# atWork_Motor_Driver.net
KiCad netlist of a schematic drawn in Altium Designer
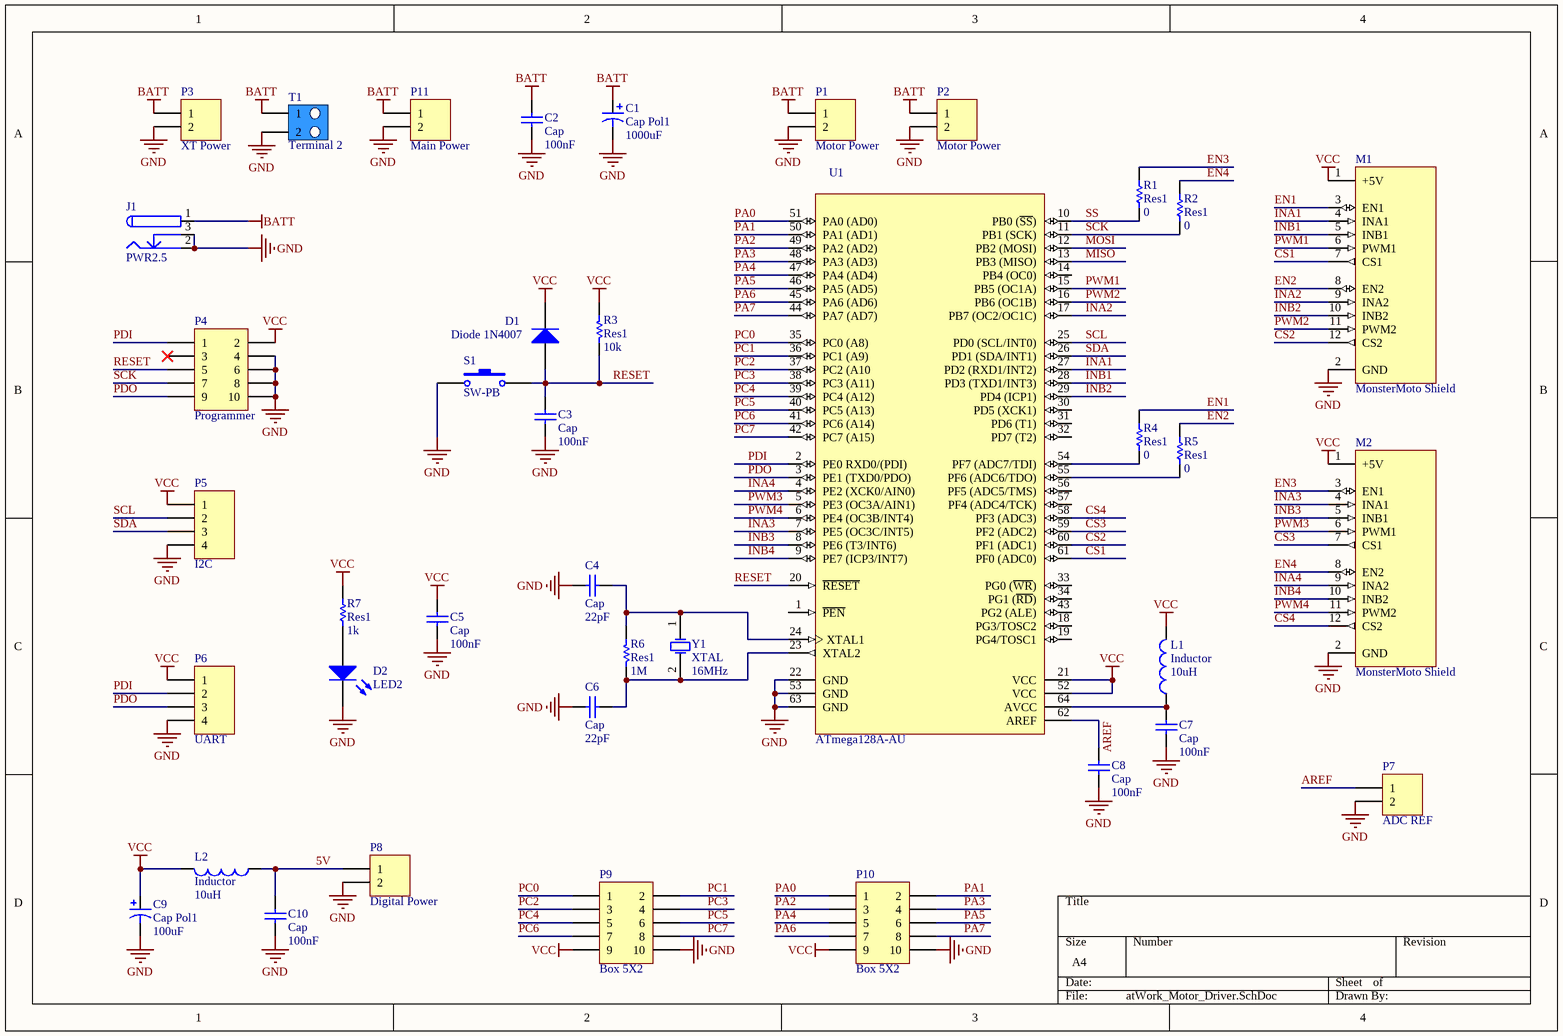
[diagram p0: atWork_Motor_Driver.SchDoc]

(export (version "E")
  (design (tool "Eeschema 10.0.6"))
  (components
    (comp (ref "C1")
      (value "Cap Pol1")
      (footprint "CAP2")
      (description "Polarized Capacitor (Radial)")
      (fields (field (name "ALTIUM_VALUE") "1000uF") (field (name "PUBLISHER") "Altium Limited"))
      (libsource (lib "Miscellaneous Devices") (part "Cap Pol1"))
    )
    (comp (ref "C2")
      (value "Cap")
      (footprint "C1206")
      (description "Capacitor")
      (fields (field (name "ALTIUM_VALUE") "100nF") (field (name "PUBLISHER") "Altium Limited"))
      (libsource (lib "Miscellaneous Devices") (part "Cap"))
    )
    (comp (ref "C3")
      (value "Cap")
      (footprint "C1206")
      (description "Capacitor")
      (fields (field (name "ALTIUM_VALUE") "100nF") (field (name "PUBLISHER") "Altium Limited"))
      (libsource (lib "Miscellaneous Devices") (part "Cap"))
    )
    (comp (ref "C4")
      (value "Cap")
      (footprint "C1206")
      (description "Capacitor")
      (fields (field (name "ALTIUM_VALUE") "22pF") (field (name "PUBLISHER") "Altium Limited"))
      (libsource (lib "Miscellaneous Devices") (part "Cap"))
    )
    (comp (ref "C5")
      (value "Cap")
      (footprint "C1206")
      (description "Capacitor")
      (fields (field (name "ALTIUM_VALUE") "100nF") (field (name "PUBLISHER") "Altium Limited"))
      (libsource (lib "Miscellaneous Devices") (part "Cap"))
    )
    (comp (ref "C6")
      (value "Cap")
      (footprint "C1206")
      (description "Capacitor")
      (fields (field (name "ALTIUM_VALUE") "22pF") (field (name "PUBLISHER") "Altium Limited"))
      (libsource (lib "Miscellaneous Devices") (part "Cap"))
    )
    (comp (ref "C7")
      (value "Cap")
      (footprint "C1206")
      (description "Capacitor")
      (fields (field (name "ALTIUM_VALUE") "100nF") (field (name "PUBLISHER") "Altium Limited"))
      (libsource (lib "Miscellaneous Devices") (part "Cap"))
    )
    (comp (ref "C8")
      (value "Cap")
      (footprint "C1206")
      (description "Capacitor")
      (fields (field (name "ALTIUM_VALUE") "100nF") (field (name "PUBLISHER") "Altium Limited"))
      (libsource (lib "Miscellaneous Devices") (part "Cap"))
    )
    (comp (ref "C9")
      (value "Cap Pol1")
      (footprint "CAP-SMD1")
      (description "Polarized Capacitor (Radial)")
      (fields (field (name "ALTIUM_VALUE") "100uF") (field (name "PUBLISHER") "Altium Limited"))
      (libsource (lib "") (part "Cap Pol1_1"))
    )
    (comp (ref "C10")
      (value "Cap")
      (footprint "C1206")
      (description "Capacitor")
      (fields (field (name "ALTIUM_VALUE") "100nF") (field (name "PUBLISHER") "Altium Limited"))
      (libsource (lib "Miscellaneous Devices") (part "Cap"))
    )
    (comp (ref "D1")
      (value "Diode 1N4007")
      (footprint "DIODE-SMD")
      (description "1 Amp General Purpose Rectifier")
      (fields (field (name "PUBLISHER") "Altium Limited"))
      (libsource (lib "Miscellaneous Devices") (part "Diode 1N4007"))
    )
    (comp (ref "D2")
      (value "LED2")
      (footprint "3.2X1.6X1.1")
      (description "Typical RED, GREEN, YELLOW, AMBER GaAs LED")
      (fields (field (name "PUBLISHER") "Altium Limited"))
      (libsource (lib "Miscellaneous Devices") (part "LED2"))
    )
    (comp (ref "J1")
      (value "PWR2.5")
      (footprint "PWR2.5")
      (description "Low Voltage Power Supply Connector")
      (fields (field (name "PUBLISHER") "Altium Limited"))
      (libsource (lib "mp") (part "PWR2.5"))
    )
    (comp (ref "L1")
      (value "Inductor")
      (footprint "C1206")
      (fields (field (name "ALTIUM_VALUE") "10uH") (field (name "PUBLISHER") "Altium Limited"))
      (libsource (lib "Miscellaneous Devices") (part "Inductor"))
    )
    (comp (ref "L2")
      (value "Inductor")
      (footprint "C1206")
      (fields (field (name "ALTIUM_VALUE") "10uH") (field (name "PUBLISHER") "Altium Limited"))
      (libsource (lib "Miscellaneous Devices") (part "Inductor"))
    )
    (comp (ref "M1")
      (value "MonsterMoto Shield")
      (footprint "MONSTERMOTO")
      (fields (field (name "DESIGNER") "Meysam Parvizi") (field (name "EMAIL") "meysam.parvizi@live.com"))
      (libsource (lib "mp") (part "MonsterMoto"))
    )
    (comp (ref "M2")
      (value "MonsterMoto Shield")
      (footprint "MONSTERMOTO")
      (fields (field (name "DESIGNER") "Meysam Parvizi") (field (name "EMAIL") "meysam.parvizi@live.com"))
      (libsource (lib "mp") (part "MonsterMoto"))
    )
    (comp (ref "P1")
      (value "Motor Power")
      (footprint "POWER2PIN")
      (description "Header, 2-Pin")
      (fields (field (name "PUBLISHER") "Altium Limited"))
      (libsource (lib "Miscellaneous Connectors") (part "Header 2"))
    )
    (comp (ref "P2")
      (value "Motor Power")
      (footprint "POWER2PIN")
      (description "Header, 2-Pin")
      (fields (field (name "PUBLISHER") "Altium Limited"))
      (libsource (lib "Miscellaneous Connectors") (part "Header 2"))
    )
    (comp (ref "P3")
      (value "XT Power")
      (footprint "XT")
      (description "Header, 2-Pin")
      (fields (field (name "PUBLISHER") "Altium Limited"))
      (libsource (lib "Miscellaneous Connectors") (part "Header 2"))
    )
    (comp (ref "P4")
      (value "Programmer")
      (footprint "BOX2X5")
      (description "Box, 5-Pin, Dual row")
      (fields (field (name "DESIGNER") "Meysam Parvizi") (field (name "EMAIL") "meysam.parvizi.ir@gmail.com"))
      (libsource (lib "mp") (part "Box 5X2"))
    )
    (comp (ref "P5")
      (value "I2C")
      (footprint "XH4PIN")
      (description "Header, 4-Pin")
      (fields (field (name "PUBLISHER") "Altium Limited"))
      (libsource (lib "Miscellaneous Connectors") (part "Header 4"))
    )
    (comp (ref "P6")
      (value "UART")
      (footprint "XH4PIN")
      (description "Header, 4-Pin")
      (fields (field (name "PUBLISHER") "Altium Limited"))
      (libsource (lib "Miscellaneous Connectors") (part "Header 4"))
    )
    (comp (ref "P7")
      (value "ADC REF")
      (footprint "XH2PIN")
      (description "Header, 2-Pin")
      (fields (field (name "PUBLISHER") "Altium Limited"))
      (libsource (lib "Miscellaneous Connectors") (part "Header 2"))
    )
    (comp (ref "P8")
      (value "Digital Power")
      (footprint "XH2PIN")
      (description "Header, 2-Pin")
      (fields (field (name "PUBLISHER") "Altium Limited"))
      (libsource (lib "Miscellaneous Connectors") (part "Header 2"))
    )
    (comp (ref "P9")
      (value "Box 5X2")
      (footprint "BOX2X5_RIGHT")
      (description "Box, 5-Pin, Dual row")
      (fields (field (name "DESIGNER") "Meysam Parvizi") (field (name "EMAIL") "meysam.parvizi.ir@gmail.com"))
      (libsource (lib "mp") (part "Box 5X2"))
    )
    (comp (ref "P10")
      (value "Box 5X2")
      (footprint "BOX2X5_RIGHT")
      (description "Box, 5-Pin, Dual row")
      (fields (field (name "DESIGNER") "Meysam Parvizi") (field (name "EMAIL") "meysam.parvizi.ir@gmail.com"))
      (libsource (lib "mp") (part "Box 5X2"))
    )
    (comp (ref "P11")
      (value "Main Power")
      (footprint "POWER2PIN")
      (description "Header, 2-Pin")
      (fields (field (name "PUBLISHER") "Altium Limited"))
      (libsource (lib "Miscellaneous Connectors") (part "Header 2"))
    )
    (comp (ref "R1")
      (value "Res1")
      (footprint "C1206")
      (description "Resistor")
      (fields (field (name "ALTIUM_VALUE") "0") (field (name "PUBLISHER") "Altium Limited"))
      (libsource (lib "Miscellaneous Devices") (part "Res1"))
    )
    (comp (ref "R2")
      (value "Res1")
      (footprint "C1206")
      (description "Resistor")
      (fields (field (name "ALTIUM_VALUE") "0") (field (name "PUBLISHER") "Altium Limited"))
      (libsource (lib "Miscellaneous Devices") (part "Res1"))
    )
    (comp (ref "R3")
      (value "Res1")
      (footprint "C1206")
      (description "Resistor")
      (fields (field (name "ALTIUM_VALUE") "10k") (field (name "PUBLISHER") "Altium Limited"))
      (libsource (lib "Miscellaneous Devices") (part "Res1"))
    )
    (comp (ref "R4")
      (value "Res1")
      (footprint "C1206")
      (description "Resistor")
      (fields (field (name "ALTIUM_VALUE") "0") (field (name "PUBLISHER") "Altium Limited"))
      (libsource (lib "Miscellaneous Devices") (part "Res1"))
    )
    (comp (ref "R5")
      (value "Res1")
      (footprint "C1206")
      (description "Resistor")
      (fields (field (name "ALTIUM_VALUE") "0") (field (name "PUBLISHER") "Altium Limited"))
      (libsource (lib "Miscellaneous Devices") (part "Res1"))
    )
    (comp (ref "R6")
      (value "Res1")
      (footprint "C1206")
      (description "Resistor")
      (fields (field (name "ALTIUM_VALUE") "1M") (field (name "PUBLISHER") "Altium Limited"))
      (libsource (lib "Miscellaneous Devices") (part "Res1"))
    )
    (comp (ref "R7")
      (value "Res1")
      (footprint "C1206")
      (description "Resistor")
      (fields (field (name "ALTIUM_VALUE") "1k") (field (name "PUBLISHER") "Altium Limited"))
      (libsource (lib "Miscellaneous Devices") (part "Res1"))
    )
    (comp (ref "S1")
      (value "SW-PB")
      (footprint "PUSH1")
      (description "Switch")
      (fields (field (name "PUBLISHER") "Altium Limited"))
      (libsource (lib "Miscellaneous Devices") (part "SW-PB"))
    )
    (comp (ref "T1")
      (value "Terminal 2")
      (footprint "TERMINAL2PIN")
      (description "Terminal, 2 pin")
      (fields (field (name "DESIGNER") "Meysam Parvizi") (field (name "EMAIL") "meysam.parvizi.ir@gmail.com"))
      (libsource (lib "mp") (part "Terminal 2"))
    )
    (comp (ref "U1")
      (value "ATmega128A-AU")
      (footprint "64A_M")
      (fields (field (name "PUBLISHER") "Altium Limited"))
      (libsource (lib "Atmel Microcontroller 8-Bit megaAVR") (part "ATmega128A-AU"))
    )
    (comp (ref "Y1")
      (value "XTAL")
      (footprint "XTAL")
      (description "Crystal Oscillator")
      (fields
        (field (name "ALTIUM_VALUE") "16MHz")
        (field (name "DESIGNER") "Meysam Parvizi")
        (field (name "EMAIL") "meysam.parvizi.ir@gmail.com")
      )
      (libsource (lib "mp") (part "XTAL"))
    )
  )
  (nets
    (net (code "1") (name "/5V") (class "Default")
      (node (ref "C10") (pin "2") (pinfunction "2_2") (pintype "passive"))
      (node (ref "L2") (pin "1") (pinfunction "1_1") (pintype "passive"))
      (node (ref "P8") (pin "1") (pinfunction "1_1") (pintype "passive"))
    )
    (net (code "2") (name "/AREF") (class "Default")
      (node (ref "C8") (pin "2") (pinfunction "2_2") (pintype "passive"))
      (node (ref "P7") (pin "1") (pinfunction "1_1") (pintype "passive"))
      (node (ref "U1") (pin "62") (pinfunction "AREF_62") (pintype "power_in"))
    )
    (net (code "3") (name "/CS1") (class "Default")
      (node (ref "M1") (pin "7") (pinfunction "CS1_7") (pintype "output"))
      (node (ref "U1") (pin "61") (pinfunction "PF0_(ADC0)_61") (pintype "bidirectional"))
    )
    (net (code "4") (name "/CS2") (class "Default")
      (node (ref "M1") (pin "12") (pinfunction "CS2_12") (pintype "output"))
      (node (ref "U1") (pin "60") (pinfunction "PF1_(ADC1)_60") (pintype "bidirectional"))
    )
    (net (code "5") (name "/CS3") (class "Default")
      (node (ref "M2") (pin "7") (pinfunction "CS1_7") (pintype "output"))
      (node (ref "U1") (pin "59") (pinfunction "PF2_(ADC2)_59") (pintype "bidirectional"))
    )
    (net (code "6") (name "/CS4") (class "Default")
      (node (ref "M2") (pin "12") (pinfunction "CS2_12") (pintype "output"))
      (node (ref "U1") (pin "58") (pinfunction "PF3_(ADC3)_58") (pintype "bidirectional"))
    )
    (net (code "7") (name "/EN1") (class "Default")
      (node (ref "M1") (pin "3") (pinfunction "EN1_3") (pintype "bidirectional"))
      (node (ref "R4") (pin "2") (pinfunction "2_2") (pintype "passive"))
    )
    (net (code "8") (name "/EN2") (class "Default")
      (node (ref "M1") (pin "8") (pinfunction "EN2_8") (pintype "bidirectional"))
      (node (ref "R5") (pin "2") (pinfunction "2_2") (pintype "passive"))
    )
    (net (code "9") (name "/EN3") (class "Default")
      (node (ref "M2") (pin "3") (pinfunction "EN1_3") (pintype "bidirectional"))
      (node (ref "R1") (pin "2") (pinfunction "2_2") (pintype "passive"))
    )
    (net (code "10") (name "/EN4") (class "Default")
      (node (ref "M2") (pin "8") (pinfunction "EN2_8") (pintype "bidirectional"))
      (node (ref "R2") (pin "2") (pinfunction "2_2") (pintype "passive"))
    )
    (net (code "11") (name "/INA1") (class "Default")
      (node (ref "M1") (pin "4") (pinfunction "INA1_4") (pintype "input"))
      (node (ref "U1") (pin "27") (pinfunction "PD2_(RXD1/INT2)_27") (pintype "bidirectional"))
    )
    (net (code "12") (name "/INA2") (class "Default")
      (node (ref "M1") (pin "9") (pinfunction "INA2_9") (pintype "input"))
      (node (ref "U1") (pin "17") (pinfunction "PB7_(OC2/OC1C)_17") (pintype "bidirectional"))
    )
    (net (code "13") (name "/INA3") (class "Default")
      (node (ref "M2") (pin "4") (pinfunction "INA1_4") (pintype "input"))
      (node (ref "U1") (pin "7") (pinfunction "PE5_(OC3C/INT5)_7") (pintype "bidirectional"))
    )
    (net (code "14") (name "/INA4") (class "Default")
      (node (ref "M2") (pin "9") (pinfunction "INA2_9") (pintype "input"))
      (node (ref "U1") (pin "4") (pinfunction "PE2_(XCK0/AIN0)_4") (pintype "bidirectional"))
    )
    (net (code "15") (name "/INB1") (class "Default")
      (node (ref "M1") (pin "5") (pinfunction "INB1_5") (pintype "input"))
      (node (ref "U1") (pin "28") (pinfunction "PD3_(TXD1/INT3)_28") (pintype "bidirectional"))
    )
    (net (code "16") (name "/INB2") (class "Default")
      (node (ref "M1") (pin "10") (pinfunction "INB2_10") (pintype "input"))
      (node (ref "U1") (pin "29") (pinfunction "PD4_(ICP1)_29") (pintype "bidirectional"))
    )
    (net (code "17") (name "/INB3") (class "Default")
      (node (ref "M2") (pin "5") (pinfunction "INB1_5") (pintype "input"))
      (node (ref "U1") (pin "8") (pinfunction "PE6_(T3/INT6)_8") (pintype "bidirectional"))
    )
    (net (code "18") (name "/INB4") (class "Default")
      (node (ref "M2") (pin "10") (pinfunction "INB2_10") (pintype "input"))
      (node (ref "U1") (pin "9") (pinfunction "PE7_(ICP3/INT7)_9") (pintype "bidirectional"))
    )
    (net (code "19") (name "/MISO") (class "Default")
      (node (ref "U1") (pin "13") (pinfunction "PB3_(MISO)_13") (pintype "bidirectional"))
    )
    (net (code "20") (name "/MOSI") (class "Default")
      (node (ref "U1") (pin "12") (pinfunction "PB2_(MOSI)_12") (pintype "bidirectional"))
    )
    (net (code "21") (name "/PA0") (class "Default")
      (node (ref "P10") (pin "1") (pinfunction "1_1") (pintype "passive"))
      (node (ref "U1") (pin "51") (pinfunction "PA0_(AD0)_51") (pintype "bidirectional"))
    )
    (net (code "22") (name "/PA1") (class "Default")
      (node (ref "P10") (pin "2") (pinfunction "2_2") (pintype "passive"))
      (node (ref "U1") (pin "50") (pinfunction "PA1_(AD1)_50") (pintype "bidirectional"))
    )
    (net (code "23") (name "/PA2") (class "Default")
      (node (ref "P10") (pin "3") (pinfunction "3_3") (pintype "passive"))
      (node (ref "U1") (pin "49") (pinfunction "PA2_(AD2)_49") (pintype "bidirectional"))
    )
    (net (code "24") (name "/PA3") (class "Default")
      (node (ref "P10") (pin "4") (pinfunction "4_4") (pintype "passive"))
      (node (ref "U1") (pin "48") (pinfunction "PA3_(AD3)_48") (pintype "bidirectional"))
    )
    (net (code "25") (name "/PA4") (class "Default")
      (node (ref "P10") (pin "5") (pinfunction "5_5") (pintype "passive"))
      (node (ref "U1") (pin "47") (pinfunction "PA4_(AD4)_47") (pintype "bidirectional"))
    )
    (net (code "26") (name "/PA5") (class "Default")
      (node (ref "P10") (pin "6") (pinfunction "6_6") (pintype "passive"))
      (node (ref "U1") (pin "46") (pinfunction "PA5_(AD5)_46") (pintype "bidirectional"))
    )
    (net (code "27") (name "/PA6") (class "Default")
      (node (ref "P10") (pin "7") (pinfunction "7_7") (pintype "passive"))
      (node (ref "U1") (pin "45") (pinfunction "PA6_(AD6)_45") (pintype "bidirectional"))
    )
    (net (code "28") (name "/PA7") (class "Default")
      (node (ref "P10") (pin "8") (pinfunction "8_8") (pintype "passive"))
      (node (ref "U1") (pin "44") (pinfunction "PA7_(AD7)_44") (pintype "bidirectional"))
    )
    (net (code "29") (name "/PC0") (class "Default")
      (node (ref "P9") (pin "1") (pinfunction "1_1") (pintype "passive"))
      (node (ref "U1") (pin "35") (pinfunction "PC0_(A8)_35") (pintype "bidirectional"))
    )
    (net (code "30") (name "/PC1") (class "Default")
      (node (ref "P9") (pin "2") (pinfunction "2_2") (pintype "passive"))
      (node (ref "U1") (pin "36") (pinfunction "PC1_(A9)_36") (pintype "bidirectional"))
    )
    (net (code "31") (name "/PC2") (class "Default")
      (node (ref "P9") (pin "3") (pinfunction "3_3") (pintype "passive"))
      (node (ref "U1") (pin "37") (pinfunction "PC2_(A10_37") (pintype "bidirectional"))
    )
    (net (code "32") (name "/PC3") (class "Default")
      (node (ref "P9") (pin "4") (pinfunction "4_4") (pintype "passive"))
      (node (ref "U1") (pin "38") (pinfunction "PC3_(A11)_38") (pintype "bidirectional"))
    )
    (net (code "33") (name "/PC4") (class "Default")
      (node (ref "P9") (pin "5") (pinfunction "5_5") (pintype "passive"))
      (node (ref "U1") (pin "39") (pinfunction "PC4_(A12)_39") (pintype "bidirectional"))
    )
    (net (code "34") (name "/PC5") (class "Default")
      (node (ref "P9") (pin "6") (pinfunction "6_6") (pintype "passive"))
      (node (ref "U1") (pin "40") (pinfunction "PC5_(A13)_40") (pintype "bidirectional"))
    )
    (net (code "35") (name "/PC6") (class "Default")
      (node (ref "P9") (pin "7") (pinfunction "7_7") (pintype "passive"))
      (node (ref "U1") (pin "41") (pinfunction "PC6_(A14)_41") (pintype "bidirectional"))
    )
    (net (code "36") (name "/PC7") (class "Default")
      (node (ref "P9") (pin "8") (pinfunction "8_8") (pintype "passive"))
      (node (ref "U1") (pin "42") (pinfunction "PC7_(A15)_42") (pintype "bidirectional"))
    )
    (net (code "37") (name "/PDI") (class "Default")
      (node (ref "P4") (pin "1") (pinfunction "1_1") (pintype "passive"))
      (node (ref "P6") (pin "2") (pinfunction "2_2") (pintype "passive"))
      (node (ref "U1") (pin "2") (pinfunction "PE0_RXD0/(PDI)_2") (pintype "bidirectional"))
    )
    (net (code "38") (name "/PDO") (class "Default")
      (node (ref "P4") (pin "9") (pinfunction "9_9") (pintype "passive"))
      (node (ref "P6") (pin "3") (pinfunction "3_3") (pintype "passive"))
      (node (ref "U1") (pin "3") (pinfunction "PE1_(TXD0/PDO)_3") (pintype "bidirectional"))
    )
    (net (code "39") (name "/PWM1") (class "Default")
      (node (ref "M1") (pin "6") (pinfunction "PWM1_6") (pintype "input"))
      (node (ref "U1") (pin "15") (pinfunction "PB5_(OC1A)_15") (pintype "bidirectional"))
    )
    (net (code "40") (name "/PWM2") (class "Default")
      (node (ref "M1") (pin "11") (pinfunction "PWM2_11") (pintype "input"))
      (node (ref "U1") (pin "16") (pinfunction "PB6_(OC1B)_16") (pintype "bidirectional"))
    )
    (net (code "41") (name "/PWM3") (class "Default")
      (node (ref "M2") (pin "6") (pinfunction "PWM1_6") (pintype "input"))
      (node (ref "U1") (pin "5") (pinfunction "PE3_(OC3A/AIN1)_5") (pintype "bidirectional"))
    )
    (net (code "42") (name "/PWM4") (class "Default")
      (node (ref "M2") (pin "11") (pinfunction "PWM2_11") (pintype "input"))
      (node (ref "U1") (pin "6") (pinfunction "PE4_(OC3B/INT4)_6") (pintype "bidirectional"))
    )
    (net (code "43") (name "/RESET") (class "Default")
      (node (ref "C3") (pin "2") (pinfunction "2_2") (pintype "passive"))
      (node (ref "D1") (pin "1") (pinfunction "A_1") (pintype "passive"))
      (node (ref "P4") (pin "5") (pinfunction "5_5") (pintype "passive"))
      (node (ref "R3") (pin "2") (pinfunction "2_2") (pintype "passive"))
      (node (ref "S1") (pin "1") (pinfunction "1_1") (pintype "passive"))
      (node (ref "U1") (pin "20") (pinfunction "~{RESET}_20") (pintype "input"))
    )
    (net (code "44") (name "/SCK") (class "Default")
      (node (ref "P4") (pin "7") (pinfunction "7_7") (pintype "passive"))
      (node (ref "R2") (pin "1") (pinfunction "1_1") (pintype "passive"))
      (node (ref "U1") (pin "11") (pinfunction "PB1_(SCK)_11") (pintype "bidirectional"))
    )
    (net (code "45") (name "/SCL") (class "Default")
      (node (ref "P5") (pin "2") (pinfunction "2_2") (pintype "passive"))
      (node (ref "U1") (pin "25") (pinfunction "PD0_(SCL/INT0)_25") (pintype "bidirectional"))
    )
    (net (code "46") (name "/SDA") (class "Default")
      (node (ref "P5") (pin "3") (pinfunction "3_3") (pintype "passive"))
      (node (ref "U1") (pin "26") (pinfunction "PD1_(SDA/INT1)_26") (pintype "bidirectional"))
    )
    (net (code "47") (name "/SS") (class "Default")
      (node (ref "R1") (pin "1") (pinfunction "1_1") (pintype "passive"))
      (node (ref "U1") (pin "10") (pinfunction "PB0_(~{SS})_10") (pintype "bidirectional"))
    )
    (net (code "48") (name "BATT") (class "Default")
      (node (ref "C1") (pin "1") (pinfunction "1_1") (pintype "passive"))
      (node (ref "C2") (pin "2") (pinfunction "2_2") (pintype "passive"))
      (node (ref "J1") (pin "1") (pinfunction "1_1") (pintype "power_in"))
      (node (ref "P1") (pin "1") (pinfunction "1_1") (pintype "passive"))
      (node (ref "P11") (pin "1") (pinfunction "1_1") (pintype "passive"))
      (node (ref "P2") (pin "1") (pinfunction "1_1") (pintype "passive"))
      (node (ref "P3") (pin "1") (pinfunction "1_1") (pintype "passive"))
      (node (ref "T1") (pin "1") (pinfunction "1_1") (pintype "passive"))
    )
    (net (code "49") (name "GND") (class "Default")
      (node (ref "C1") (pin "2") (pinfunction "2_2") (pintype "passive"))
      (node (ref "C10") (pin "1") (pinfunction "1_1") (pintype "passive"))
      (node (ref "C2") (pin "1") (pinfunction "1_1") (pintype "passive"))
      (node (ref "C3") (pin "1") (pinfunction "1_1") (pintype "passive"))
      (node (ref "C4") (pin "1") (pinfunction "1_1") (pintype "passive"))
      (node (ref "C5") (pin "1") (pinfunction "1_1") (pintype "passive"))
      (node (ref "C6") (pin "1") (pinfunction "1_1") (pintype "passive"))
      (node (ref "C7") (pin "1") (pinfunction "1_1") (pintype "passive"))
      (node (ref "C8") (pin "1") (pinfunction "1_1") (pintype "passive"))
      (node (ref "C9") (pin "2") (pinfunction "2_2") (pintype "passive"))
      (node (ref "D2") (pin "2") (pinfunction "K_2") (pintype "passive"))
      (node (ref "J1") (pin "2") (pinfunction "2_2") (pintype "power_in"))
      (node (ref "J1") (pin "3") (pinfunction "3_3") (pintype "power_in"))
      (node (ref "M1") (pin "2") (pinfunction "GND_2") (pintype "power_in"))
      (node (ref "M2") (pin "2") (pinfunction "GND_2") (pintype "power_in"))
      (node (ref "P1") (pin "2") (pinfunction "2_2") (pintype "passive"))
      (node (ref "P10") (pin "10") (pinfunction "10_10") (pintype "passive"))
      (node (ref "P11") (pin "2") (pinfunction "2_2") (pintype "passive"))
      (node (ref "P2") (pin "2") (pinfunction "2_2") (pintype "passive"))
      (node (ref "P3") (pin "2") (pinfunction "2_2") (pintype "passive"))
      (node (ref "P4") (pin "10") (pinfunction "10_10") (pintype "passive"))
      (node (ref "P4") (pin "4") (pinfunction "4_4") (pintype "passive"))
      (node (ref "P4") (pin "6") (pinfunction "6_6") (pintype "passive"))
      (node (ref "P4") (pin "8") (pinfunction "8_8") (pintype "passive"))
      (node (ref "P5") (pin "4") (pinfunction "4_4") (pintype "passive"))
      (node (ref "P6") (pin "4") (pinfunction "4_4") (pintype "passive"))
      (node (ref "P7") (pin "2") (pinfunction "2_2") (pintype "passive"))
      (node (ref "P8") (pin "2") (pinfunction "2_2") (pintype "passive"))
      (node (ref "P9") (pin "10") (pinfunction "10_10") (pintype "passive"))
      (node (ref "S1") (pin "2") (pinfunction "2_2") (pintype "passive"))
      (node (ref "T1") (pin "2") (pinfunction "2_2") (pintype "passive"))
      (node (ref "U1") (pin "22") (pinfunction "GND_22") (pintype "power_in"))
      (node (ref "U1") (pin "53") (pinfunction "GND_53") (pintype "power_in"))
      (node (ref "U1") (pin "63") (pinfunction "GND_63") (pintype "power_in"))
    )
    (net (code "50") (name "Net-(D2-A)") (class "Default")
      (node (ref "D2") (pin "1") (pinfunction "A_1") (pintype "passive"))
      (node (ref "R7") (pin "1") (pinfunction "1_1") (pintype "passive"))
    )
    (net (code "51") (name "Net-(U1-AVCC)") (class "Default")
      (node (ref "C7") (pin "2") (pinfunction "2_2") (pintype "passive"))
      (node (ref "L1") (pin "1") (pinfunction "1_1") (pintype "passive"))
      (node (ref "U1") (pin "64") (pinfunction "AVCC_64") (pintype "power_in"))
    )
    (net (code "52") (name "Net-(U1-PF6_(ADC6{slash}TDO))") (class "Default")
      (node (ref "R5") (pin "1") (pinfunction "1_1") (pintype "passive"))
      (node (ref "U1") (pin "55") (pinfunction "PF6_(ADC6/TDO)_55") (pintype "bidirectional"))
    )
    (net (code "53") (name "Net-(U1-PF7_(ADC7{slash}TDI))") (class "Default")
      (node (ref "R4") (pin "1") (pinfunction "1_1") (pintype "passive"))
      (node (ref "U1") (pin "54") (pinfunction "PF7_(ADC7/TDI)_54") (pintype "bidirectional"))
    )
    (net (code "54") (name "Net-(U1-XTAL1)") (class "Default")
      (node (ref "C4") (pin "2") (pinfunction "2_2") (pintype "passive"))
      (node (ref "R6") (pin "1") (pinfunction "1_1") (pintype "passive"))
      (node (ref "U1") (pin "24") (pinfunction "XTAL1_24") (pintype "input"))
      (node (ref "Y1") (pin "1") (pinfunction "OSC1_1") (pintype "passive"))
    )
    (net (code "55") (name "Net-(U1-XTAL2)") (class "Default")
      (node (ref "C6") (pin "2") (pinfunction "2_2") (pintype "passive"))
      (node (ref "R6") (pin "2") (pinfunction "2_2") (pintype "passive"))
      (node (ref "U1") (pin "23") (pinfunction "XTAL2_23") (pintype "output"))
      (node (ref "Y1") (pin "2") (pinfunction "OSC2_2") (pintype "passive"))
    )
    (net (code "56") (name "VCC") (class "Default")
      (node (ref "C5") (pin "2") (pinfunction "2_2") (pintype "passive"))
      (node (ref "C9") (pin "1") (pinfunction "1_1") (pintype "passive"))
      (node (ref "D1") (pin "2") (pinfunction "K_2") (pintype "passive"))
      (node (ref "L1") (pin "2") (pinfunction "2_2") (pintype "passive"))
      (node (ref "L2") (pin "2") (pinfunction "2_2") (pintype "passive"))
      (node (ref "M1") (pin "1") (pinfunction "+5V_1") (pintype "power_in"))
      (node (ref "M2") (pin "1") (pinfunction "+5V_1") (pintype "power_in"))
      (node (ref "P10") (pin "9") (pinfunction "9_9") (pintype "passive"))
      (node (ref "P4") (pin "2") (pinfunction "2_2") (pintype "passive"))
      (node (ref "P5") (pin "1") (pinfunction "1_1") (pintype "passive"))
      (node (ref "P6") (pin "1") (pinfunction "1_1") (pintype "passive"))
      (node (ref "P9") (pin "9") (pinfunction "9_9") (pintype "passive"))
      (node (ref "R3") (pin "1") (pinfunction "1_1") (pintype "passive"))
      (node (ref "R7") (pin "2") (pinfunction "2_2") (pintype "passive"))
      (node (ref "U1") (pin "21") (pinfunction "VCC_21") (pintype "power_in"))
      (node (ref "U1") (pin "52") (pinfunction "VCC_52") (pintype "power_in"))
    )
    (net (code "57") (name "unconnected-(P4-Pad3)") (class "Default")
      (node (ref "P4") (pin "3") (pinfunction "3_3") (pintype "passive+no_connect"))
    )
    (net (code "58") (name "unconnected-(U1-PB4_(OC0)-Pad14)") (class "Default")
      (node (ref "U1") (pin "14") (pinfunction "PB4_(OC0)_14") (pintype "bidirectional"))
    )
    (net (code "59") (name "unconnected-(U1-PD5_(XCK1)-Pad30)") (class "Default")
      (node (ref "U1") (pin "30") (pinfunction "PD5_(XCK1)_30") (pintype "bidirectional"))
    )
    (net (code "60") (name "unconnected-(U1-PD6_(T1)-Pad31)") (class "Default")
      (node (ref "U1") (pin "31") (pinfunction "PD6_(T1)_31") (pintype "bidirectional"))
    )
    (net (code "61") (name "unconnected-(U1-PD7_(T2)-Pad32)") (class "Default")
      (node (ref "U1") (pin "32") (pinfunction "PD7_(T2)_32") (pintype "bidirectional"))
    )
    (net (code "62") (name "unconnected-(U1-PF4_(ADC4{slash}TCK)-Pad57)") (class "Default")
      (node (ref "U1") (pin "57") (pinfunction "PF4_(ADC4/TCK)_57") (pintype "bidirectional"))
    )
    (net (code "63") (name "unconnected-(U1-PF5_(ADC5{slash}TMS)-Pad56)") (class "Default")
      (node (ref "U1") (pin "56") (pinfunction "PF5_(ADC5/TMS)_56") (pintype "bidirectional"))
    )
    (net (code "64") (name "unconnected-(U1-PG0_(~{WR})-Pad33)") (class "Default")
      (node (ref "U1") (pin "33") (pinfunction "PG0_(~{WR})_33") (pintype "bidirectional"))
    )
    (net (code "65") (name "unconnected-(U1-PG1_(~{RD})-Pad34)") (class "Default")
      (node (ref "U1") (pin "34") (pinfunction "PG1_(~{RD})_34") (pintype "bidirectional"))
    )
    (net (code "66") (name "unconnected-(U1-PG2_(ALE)-Pad43)") (class "Default")
      (node (ref "U1") (pin "43") (pinfunction "PG2_(ALE)_43") (pintype "bidirectional"))
    )
    (net (code "67") (name "unconnected-(U1-PG3{slash}TOSC2-Pad18)") (class "Default")
      (node (ref "U1") (pin "18") (pinfunction "PG3/TOSC2_18") (pintype "bidirectional"))
    )
    (net (code "68") (name "unconnected-(U1-PG4{slash}TOSC1-Pad19)") (class "Default")
      (node (ref "U1") (pin "19") (pinfunction "PG4/TOSC1_19") (pintype "bidirectional"))
    )
    (net (code "69") (name "unconnected-(U1-~{PEN}-Pad1)") (class "Default")
      (node (ref "U1") (pin "1") (pinfunction "~{PEN}_1") (pintype "input"))
    )
  )
)
